# ttn_mad_v2_2.net
KiCad netlist of a schematic drawn in EAGLE
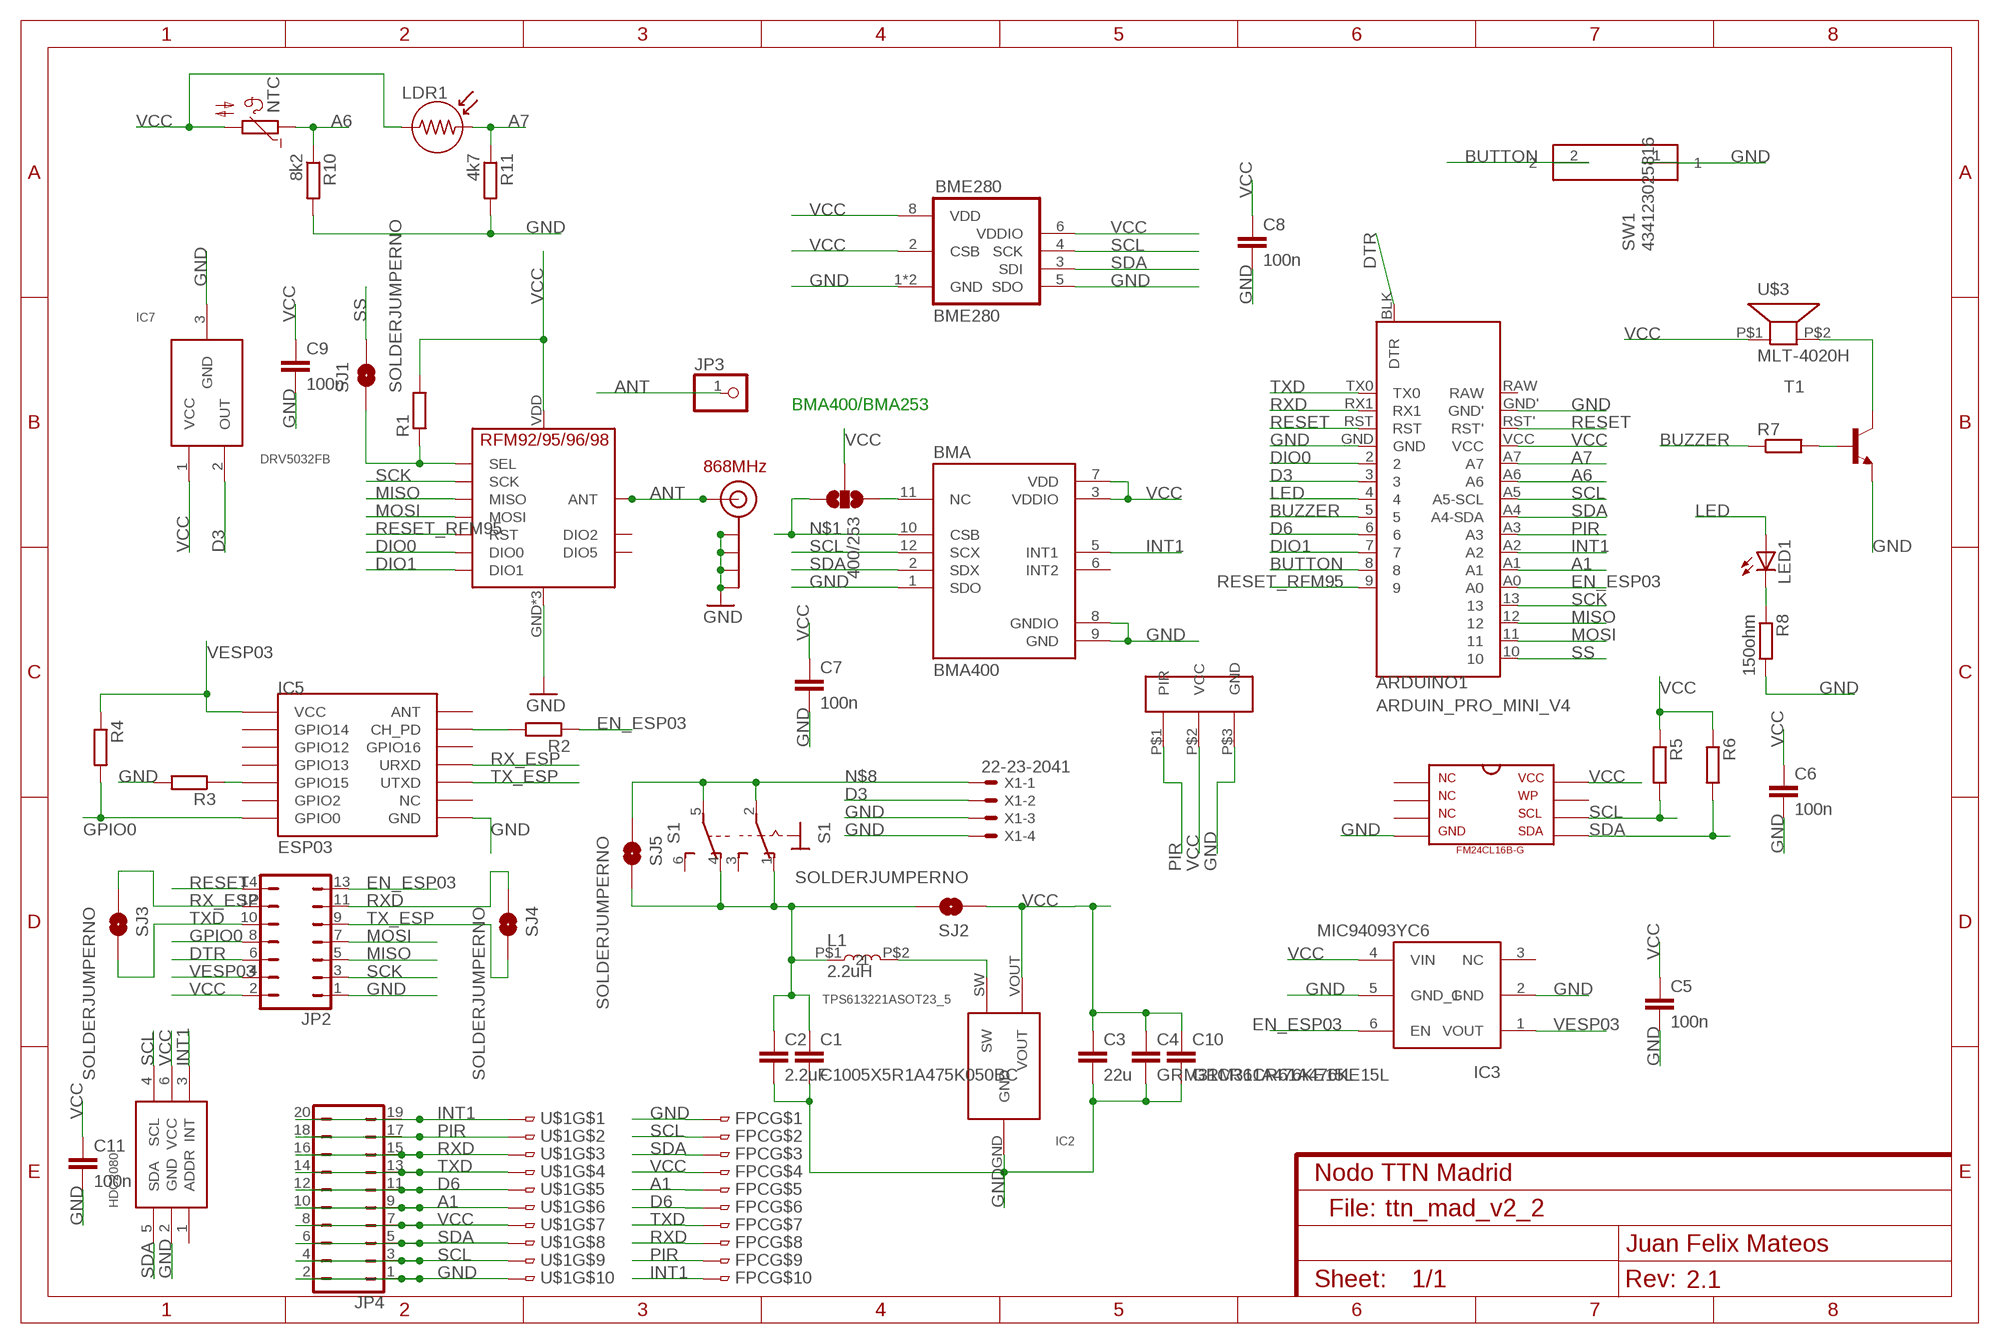
[diagram p0: schematic, sheet 1]

(export (version "E")
  (design (tool "Eeschema 10.0.6"))
  (components
    (comp (ref "400/253")
      (value "SOLDERJUMPER_2WAYT")
      (footprint "eagle-import:SJ_2")
      (libsource (lib "eagle-import") (part "SOLDERJUMPER_2WAYT"))
    )
    (comp (ref "ARDUINO1")
      (value "ARDUIN_PRO_MINI_V4")
      (footprint "eagle-import:ARDUINO_PRO_MINI_V4")
      (libsource (lib "eagle-import") (part "ARDUIN_PRO_MINI_V4"))
    )
    (comp (ref "BMA")
      (value "BMA400")
      (footprint "eagle-import:IC_BMA400")
      (fields (field (name "MF") "Bosch Sensortec"))
      (libsource (lib "eagle-import") (part "BMA400"))
    )
    (comp (ref "BME280")
      (value "BME280")
      (footprint "eagle-import:BME280")
      (libsource (lib "eagle-import") (part "BME280"))
    )
    (comp (ref "C1")
      (value "C1005X5R1A475K050BC")
      (footprint "eagle-import:C0603")
      (libsource (lib "eagle-import") (part "C-EUC0603"))
    )
    (comp (ref "C2")
      (value "2.2uF")
      (footprint "eagle-import:C0603")
      (libsource (lib "eagle-import") (part "C-EUC0603"))
    )
    (comp (ref "C3")
      (value "22u")
      (footprint "eagle-import:C0805")
      (libsource (lib "eagle-import") (part "C-EUC0805"))
    )
    (comp (ref "C4")
      (value "GRM31CR61A476KE15L")
      (footprint "eagle-import:C0805")
      (libsource (lib "eagle-import") (part "C-EUC0805"))
    )
    (comp (ref "C5")
      (value "100n")
      (footprint "eagle-import:C0603")
      (libsource (lib "eagle-import") (part "C-EUC0603"))
    )
    (comp (ref "C6")
      (value "100n")
      (footprint "eagle-import:C0603")
      (libsource (lib "eagle-import") (part "C-EUC0603"))
    )
    (comp (ref "C7")
      (value "100n")
      (footprint "eagle-import:C0603")
      (libsource (lib "eagle-import") (part "C-EUC0603"))
    )
    (comp (ref "C8")
      (value "100n")
      (footprint "eagle-import:C0603")
      (libsource (lib "eagle-import") (part "C-EUC0603"))
    )
    (comp (ref "C9")
      (value "100n")
      (footprint "eagle-import:C0603")
      (libsource (lib "eagle-import") (part "C-EUC0603"))
    )
    (comp (ref "C10")
      (value "GRM31CR61A476KE15L")
      (footprint "eagle-import:C0805")
      (libsource (lib "eagle-import") (part "C-EUC0805"))
    )
    (comp (ref "C11")
      (value "100n")
      (footprint "eagle-import:C0603")
      (libsource (lib "eagle-import") (part "C-EUC0603"))
    )
    (comp (ref "FM24")
      (value "FM24CL16B-G")
      (footprint "eagle-import:FM24CL16B-G")
      (libsource (lib "eagle-import") (part "FM24CL16B-G"))
    )
    (comp (ref "FPC")
      (value "FPC_10P_0_5MM")
      (footprint "eagle-import:FH12-10S-0.5SH")
      (libsource (lib "eagle-import") (part "FPC_10P_0_5MM"))
    )
    (comp (ref "HDC2080")
      (value "HDC2080")
      (footprint "eagle-import:WSON-6")
      (libsource (lib "eagle-import") (part "HDC2080"))
    )
    (comp (ref "IC2")
      (value "TPS613221ASOT23_5")
      (footprint "eagle-import:SOT23-5L")
      (libsource (lib "eagle-import") (part "TPS613221ASOT23_5"))
    )
    (comp (ref "IC3")
      (value "MIC94093YC6")
      (footprint "eagle-import:SC70-6")
      (libsource (lib "eagle-import") (part "MIC94093YC6"))
    )
    (comp (ref "IC5")
      (value "ESP03")
      (footprint "eagle-import:ESP03")
      (libsource (lib "eagle-import") (part "ESP03"))
    )
    (comp (ref "IC7")
      (value "DRV5032FB")
      (footprint "eagle-import:SOT23")
      (libsource (lib "eagle-import") (part "DRV5032FB"))
    )
    (comp (ref "J$2")
      (value "ANTENNATINY")
      (footprint "eagle-import:SMA_UFL_PAD_TINY")
      (libsource (lib "eagle-import") (part "ANTENNATINY"))
    )
    (comp (ref "JP2")
      (value "JP7Q")
      (footprint "eagle-import:JP7Q")
      (libsource (lib "eagle-import") (part "JP7Q"))
    )
    (comp (ref "JP3")
      (value "PINHD-1X1")
      (footprint "eagle-import:1X01")
      (libsource (lib "eagle-import") (part "PINHD-1X1"))
    )
    (comp (ref "JP4")
      (value "JP10Q")
      (footprint "eagle-import:JP10Q")
      (libsource (lib "eagle-import") (part "JP10Q"))
    )
    (comp (ref "L1")
      (value "2.2uH")
      (footprint "eagle-import:SRN2512")
      (libsource (lib "eagle-import") (part "SRN2512"))
    )
    (comp (ref "LDR1")
      (value "LDR")
      (footprint "eagle-import:LDR")
      (libsource (lib "eagle-import") (part "LDR"))
    )
    (comp (ref "LED1")
      (value "LEDSMT1206")
      (footprint "eagle-import:1206")
      (libsource (lib "eagle-import") (part "LEDSMT1206"))
    )
    (comp (ref "NTC")
      (value "NTC640")
      (footprint "eagle-import:P640")
      (libsource (lib "eagle-import") (part "NTC640"))
    )
    (comp (ref "R1")
      (value "R-EU_R0603")
      (footprint "eagle-import:R0603")
      (libsource (lib "eagle-import") (part "R-EU_R0603"))
    )
    (comp (ref "R2")
      (value "R-EU_R0603")
      (footprint "eagle-import:R0603")
      (libsource (lib "eagle-import") (part "R-EU_R0603"))
    )
    (comp (ref "R3")
      (value "R-EU_R0603")
      (footprint "eagle-import:R0603")
      (libsource (lib "eagle-import") (part "R-EU_R0603"))
    )
    (comp (ref "R4")
      (value "R-EU_R0603")
      (footprint "eagle-import:R0603")
      (libsource (lib "eagle-import") (part "R-EU_R0603"))
    )
    (comp (ref "R5")
      (value "R-EU_R0603")
      (footprint "eagle-import:R0603")
      (libsource (lib "eagle-import") (part "R-EU_R0603"))
    )
    (comp (ref "R6")
      (value "R-EU_R0603")
      (footprint "eagle-import:R0603")
      (libsource (lib "eagle-import") (part "R-EU_R0603"))
    )
    (comp (ref "R7")
      (value "R-EU_R0603")
      (footprint "eagle-import:R0603")
      (libsource (lib "eagle-import") (part "R-EU_R0603"))
    )
    (comp (ref "R8")
      (value "150ohm")
      (footprint "eagle-import:R0603")
      (libsource (lib "eagle-import") (part "R-EU_R0603"))
    )
    (comp (ref "R10")
      (value "8k2")
      (footprint "eagle-import:R0603")
      (libsource (lib "eagle-import") (part "R-EU_R0603"))
    )
    (comp (ref "R11")
      (value "4k7")
      (footprint "eagle-import:R0603")
      (libsource (lib "eagle-import") (part "R-EU_R0603"))
    )
    (comp (ref "S1")
      (value "TOGGLE_SWITCHTS_SMD")
      (footprint "eagle-import:TOGGLE_SWITCH_SMD")
      (libsource (lib "eagle-import") (part "TOGGLE_SWITCHTS_SMD"))
    )
    (comp (ref "SJ1")
      (value "SOLDERJUMPERNO")
      (footprint "eagle-import:SJ_2S-NO")
      (libsource (lib "eagle-import") (part "SOLDERJUMPERNO"))
    )
    (comp (ref "SJ2")
      (value "SOLDERJUMPERNO")
      (footprint "eagle-import:SJ_2S-NO")
      (libsource (lib "eagle-import") (part "SOLDERJUMPERNO"))
    )
    (comp (ref "SJ3")
      (value "SOLDERJUMPERNO")
      (footprint "eagle-import:SJ_2S-NO")
      (libsource (lib "eagle-import") (part "SOLDERJUMPERNO"))
    )
    (comp (ref "SJ4")
      (value "SOLDERJUMPERNO")
      (footprint "eagle-import:SJ_2S-NO")
      (libsource (lib "eagle-import") (part "SOLDERJUMPERNO"))
    )
    (comp (ref "SJ5")
      (value "SOLDERJUMPERNO")
      (footprint "eagle-import:SJ_2S-NO")
      (libsource (lib "eagle-import") (part "SOLDERJUMPERNO"))
    )
    (comp (ref "SW1")
      (value "434123025816")
      (footprint "eagle-import:434123025816")
      (libsource (lib "eagle-import") (part "434123025816"))
    )
    (comp (ref "T1")
      (value "BC817-16-NPN-SOT23-BEC")
      (footprint "eagle-import:SOT23-BEC")
      (libsource (lib "eagle-import") (part "-NPN-SOT23-BECBC817-16"))
    )
    (comp (ref "U$1")
      (value "FPC_10P_0_5MM")
      (footprint "eagle-import:FH12-10S-0.5SH")
      (libsource (lib "eagle-import") (part "FPC_10P_0_5MM"))
    )
    (comp (ref "U$3")
      (value "MLT-4020H")
      (footprint "eagle-import:MLT-4020H")
      (libsource (lib "eagle-import") (part "MLT-4020H"))
    )
    (comp (ref "U$5")
      (value "RFM95")
      (footprint "eagle-import:RFM95")
      (libsource (lib "eagle-import") (part "RFM95"))
    )
    (comp (ref "U$6")
      (value "PIR")
      (footprint "eagle-import:PIR")
      (libsource (lib "eagle-import") (part "PIR"))
    )
    (comp (ref "X1")
      (value "22-23-2041")
      (footprint "eagle-import:22-23-2041")
      (fields (field (name "MF") "MOLEX"))
      (libsource (lib "eagle-import") (part "22-23-2041"))
    )
  )
  (nets
    (net (code "1") (name "/A1") (class "Default")
      (node (ref "ARDUINO1") (pin "A1") (pinfunction "A1_A1") (pintype "bidirectional"))
      (node (ref "FPC") (pin "5") (pinfunction "1_5") (pintype "passive"))
      (node (ref "JP4") (pin "10") (pinfunction "10_10") (pintype "passive"))
      (node (ref "JP4") (pin "9") (pinfunction "9_9") (pintype "passive"))
      (node (ref "U$1") (pin "6") (pinfunction "1_6") (pintype "passive"))
    )
    (net (code "2") (name "/A6") (class "Default")
      (node (ref "ARDUINO1") (pin "A6") (pinfunction "A6_A6") (pintype "bidirectional"))
      (node (ref "NTC") (pin "1") (pinfunction "1_1") (pintype "passive"))
      (node (ref "R10") (pin "1") (pinfunction "1_1") (pintype "passive"))
    )
    (net (code "3") (name "/A7") (class "Default")
      (node (ref "ARDUINO1") (pin "A7") (pinfunction "A7_A7") (pintype "bidirectional"))
      (node (ref "LDR1") (pin "2") (pinfunction "2_2") (pintype "passive"))
      (node (ref "R11") (pin "1") (pinfunction "1_1") (pintype "passive"))
    )
    (net (code "4") (name "/ANT") (class "Default")
      (node (ref "J$2") (pin "ANT1") (pinfunction "SIGNAL_ANT1") (pintype "bidirectional"))
      (node (ref "J$2") (pin "ANT2") (pinfunction "SIGNAL_ANT2") (pintype "bidirectional"))
      (node (ref "J$2") (pin "ANT3") (pinfunction "SIGNAL_ANT3") (pintype "bidirectional"))
      (node (ref "JP3") (pin "1") (pinfunction "1_1") (pintype "passive"))
      (node (ref "U$5") (pin "ANT") (pinfunction "ANT_ANT") (pintype "passive"))
    )
    (net (code "5") (name "/BUTTON") (class "Default")
      (node (ref "ARDUINO1") (pin "8") (pinfunction "8_8") (pintype "bidirectional"))
      (node (ref "SW1") (pin "2") (pinfunction "2_2") (pintype "bidirectional"))
    )
    (net (code "6") (name "/BUZZER") (class "Default")
      (node (ref "ARDUINO1") (pin "5") (pinfunction "5_5") (pintype "bidirectional"))
      (node (ref "R7") (pin "1") (pinfunction "1_1") (pintype "passive"))
    )
    (net (code "7") (name "/D3") (class "Default")
      (node (ref "ARDUINO1") (pin "3") (pinfunction "3_3") (pintype "bidirectional"))
      (node (ref "IC7") (pin "2") (pinfunction "OUT_2") (pintype "bidirectional"))
      (node (ref "X1") (pin "2") (pinfunction "S_2") (pintype "passive"))
    )
    (net (code "8") (name "/D6") (class "Default")
      (node (ref "ARDUINO1") (pin "6") (pinfunction "6_6") (pintype "bidirectional"))
      (node (ref "FPC") (pin "6") (pinfunction "1_6") (pintype "passive"))
      (node (ref "JP4") (pin "11") (pinfunction "11_11") (pintype "passive"))
      (node (ref "JP4") (pin "12") (pinfunction "12_12") (pintype "passive"))
      (node (ref "U$1") (pin "5") (pinfunction "1_5") (pintype "passive"))
    )
    (net (code "9") (name "/DIO0") (class "Default")
      (node (ref "ARDUINO1") (pin "2") (pinfunction "2_2") (pintype "bidirectional"))
      (node (ref "U$5") (pin "DIO0") (pinfunction "DIO0_DIO0") (pintype "open_collector"))
    )
    (net (code "10") (name "/DIO1") (class "Default")
      (node (ref "ARDUINO1") (pin "7") (pinfunction "7_7") (pintype "bidirectional"))
      (node (ref "U$5") (pin "DIO1") (pinfunction "DIO1_DIO1") (pintype "open_collector"))
    )
    (net (code "11") (name "/DTR") (class "Default")
      (node (ref "ARDUINO1") (pin "BLK") (pinfunction "DTR_BLK") (pintype "bidirectional"))
      (node (ref "JP2") (pin "6") (pinfunction "6_6") (pintype "passive"))
    )
    (net (code "12") (name "/EN_ESP03") (class "Default")
      (node (ref "ARDUINO1") (pin "A0") (pinfunction "A0_A0") (pintype "bidirectional"))
      (node (ref "IC3") (pin "6") (pinfunction "EN_6") (pintype "bidirectional"))
      (node (ref "JP2") (pin "13") (pinfunction "13_13") (pintype "passive"))
      (node (ref "R2") (pin "1") (pinfunction "1_1") (pintype "passive"))
    )
    (net (code "13") (name "/GPIO0") (class "Default")
      (node (ref "IC5") (pin "GPIO0") (pinfunction "GPIO0_GPIO0") (pintype "bidirectional"))
      (node (ref "JP2") (pin "8") (pinfunction "8_8") (pintype "passive"))
      (node (ref "R4") (pin "2") (pinfunction "2_2") (pintype "passive"))
    )
    (net (code "14") (name "/INT1") (class "Default")
      (node (ref "ARDUINO1") (pin "A2") (pinfunction "A2_A2") (pintype "bidirectional"))
      (node (ref "BMA") (pin "5") (pinfunction "INT1_5") (pintype "bidirectional"))
      (node (ref "FPC") (pin "10") (pinfunction "1_10") (pintype "passive"))
      (node (ref "HDC2080") (pin "3") (pinfunction "INT_3") (pintype "bidirectional"))
      (node (ref "JP4") (pin "19") (pinfunction "19_19") (pintype "passive"))
      (node (ref "JP4") (pin "20") (pinfunction "20_20") (pintype "passive"))
      (node (ref "U$1") (pin "1") (pinfunction "1_1") (pintype "passive"))
    )
    (net (code "15") (name "/LED") (class "Default")
      (node (ref "ARDUINO1") (pin "4") (pinfunction "4_4") (pintype "bidirectional"))
      (node (ref "LED1") (pin "A") (pinfunction "A_A") (pintype "passive"))
    )
    (net (code "16") (name "/MISO") (class "Default")
      (node (ref "ARDUINO1") (pin "12") (pinfunction "12_12") (pintype "bidirectional"))
      (node (ref "JP2") (pin "5") (pinfunction "5_5") (pintype "passive"))
      (node (ref "U$5") (pin "MISO") (pinfunction "MISO_MISO") (pintype "input"))
    )
    (net (code "17") (name "/MOSI") (class "Default")
      (node (ref "ARDUINO1") (pin "11") (pinfunction "11_11") (pintype "bidirectional"))
      (node (ref "JP2") (pin "7") (pinfunction "7_7") (pintype "passive"))
      (node (ref "U$5") (pin "MOSI") (pinfunction "MOSI_MOSI") (pintype "output"))
    )
    (net (code "18") (name "/N$1") (class "Default")
      (node (ref "400/253") (pin "3") (pinfunction "3_3") (pintype "passive"))
      (node (ref "BMA") (pin "10") (pinfunction "CSB_10") (pintype "input"))
    )
    (net (code "19") (name "/N$8") (class "Default")
      (node (ref "S1") (pin "2") (pinfunction "P_2") (pintype "passive"))
      (node (ref "S1") (pin "5") (pinfunction "P_5") (pintype "passive"))
      (node (ref "SJ5") (pin "1") (pinfunction "1_1") (pintype "passive"))
      (node (ref "X1") (pin "1") (pinfunction "S_1") (pintype "passive"))
    )
    (net (code "20") (name "/PIR") (class "Default")
      (node (ref "ARDUINO1") (pin "A3") (pinfunction "A3_A3") (pintype "bidirectional"))
      (node (ref "FPC") (pin "9") (pinfunction "1_9") (pintype "passive"))
      (node (ref "JP4") (pin "17") (pinfunction "17_17") (pintype "passive"))
      (node (ref "JP4") (pin "18") (pinfunction "18_18") (pintype "passive"))
      (node (ref "U$1") (pin "2") (pinfunction "1_2") (pintype "passive"))
      (node (ref "U$6") (pin "P$1") (pinfunction "PIR_P$1") (pintype "bidirectional"))
    )
    (net (code "21") (name "/RESET") (class "Default")
      (node (ref "ARDUINO1") (pin "RST") (pinfunction "RST_RST") (pintype "bidirectional"))
      (node (ref "ARDUINO1") (pin "RST'") (pinfunction "RST'_RST'") (pintype "bidirectional"))
      (node (ref "JP2") (pin "14") (pinfunction "14_14") (pintype "passive"))
    )
    (net (code "22") (name "/RESET_RFM95") (class "Default")
      (node (ref "ARDUINO1") (pin "9") (pinfunction "9_9") (pintype "bidirectional"))
      (node (ref "U$5") (pin "RST") (pinfunction "RST_RST") (pintype "open_collector"))
    )
    (net (code "23") (name "/RXD") (class "Default")
      (node (ref "ARDUINO1") (pin "RX1") (pinfunction "RX1_RX1") (pintype "bidirectional"))
      (node (ref "FPC") (pin "8") (pinfunction "1_8") (pintype "passive"))
      (node (ref "JP2") (pin "11") (pinfunction "11_11") (pintype "passive"))
      (node (ref "JP4") (pin "15") (pinfunction "15_15") (pintype "passive"))
      (node (ref "JP4") (pin "16") (pinfunction "16_16") (pintype "passive"))
      (node (ref "SJ4") (pin "1") (pinfunction "1_1") (pintype "passive"))
      (node (ref "U$1") (pin "3") (pinfunction "1_3") (pintype "passive"))
    )
    (net (code "24") (name "/RX_ESP") (class "Default")
      (node (ref "IC5") (pin "URXD") (pinfunction "URXD_URXD") (pintype "bidirectional"))
      (node (ref "JP2") (pin "12") (pinfunction "12_12") (pintype "passive"))
      (node (ref "SJ3") (pin "1") (pinfunction "1_1") (pintype "passive"))
    )
    (net (code "25") (name "/SCK") (class "Default")
      (node (ref "ARDUINO1") (pin "13") (pinfunction "13_13") (pintype "bidirectional"))
      (node (ref "JP2") (pin "3") (pinfunction "3_3") (pintype "passive"))
      (node (ref "U$5") (pin "SCK") (pinfunction "SCK_SCK") (pintype "input"))
    )
    (net (code "26") (name "/SCL") (class "Default")
      (node (ref "ARDUINO1") (pin "A5") (pinfunction "A5-SCL_A5") (pintype "bidirectional"))
      (node (ref "BMA") (pin "12") (pinfunction "SCX_12") (pintype "input"))
      (node (ref "BME280") (pin "4") (pinfunction "SCK_4") (pintype "bidirectional"))
      (node (ref "FM24") (pin "6") (pinfunction "6_6") (pintype "input"))
      (node (ref "FPC") (pin "2") (pinfunction "1_2") (pintype "passive"))
      (node (ref "HDC2080") (pin "4") (pinfunction "SCL_4") (pintype "bidirectional"))
      (node (ref "JP4") (pin "3") (pinfunction "3_3") (pintype "passive"))
      (node (ref "JP4") (pin "4") (pinfunction "4_4") (pintype "passive"))
      (node (ref "R5") (pin "2") (pinfunction "2_2") (pintype "passive"))
      (node (ref "U$1") (pin "9") (pinfunction "1_9") (pintype "passive"))
    )
    (net (code "27") (name "/SDA") (class "Default")
      (node (ref "ARDUINO1") (pin "A4") (pinfunction "A4-SDA_A4") (pintype "bidirectional"))
      (node (ref "BMA") (pin "2") (pinfunction "SDX_2") (pintype "bidirectional"))
      (node (ref "BME280") (pin "3") (pinfunction "SDI_3") (pintype "bidirectional"))
      (node (ref "FM24") (pin "5") (pinfunction "5_5") (pintype "input"))
      (node (ref "FPC") (pin "3") (pinfunction "1_3") (pintype "passive"))
      (node (ref "HDC2080") (pin "5") (pinfunction "SDA_5") (pintype "bidirectional"))
      (node (ref "JP4") (pin "5") (pinfunction "5_5") (pintype "passive"))
      (node (ref "JP4") (pin "6") (pinfunction "6_6") (pintype "passive"))
      (node (ref "R6") (pin "2") (pinfunction "2_2") (pintype "passive"))
      (node (ref "U$1") (pin "8") (pinfunction "1_8") (pintype "passive"))
    )
    (net (code "28") (name "/SS") (class "Default")
      (node (ref "ARDUINO1") (pin "10") (pinfunction "10_10") (pintype "bidirectional"))
      (node (ref "SJ1") (pin "2") (pinfunction "2_2") (pintype "passive"))
    )
    (net (code "29") (name "/TXD") (class "Default")
      (node (ref "ARDUINO1") (pin "TX0") (pinfunction "TX0_TX0") (pintype "bidirectional"))
      (node (ref "FPC") (pin "7") (pinfunction "1_7") (pintype "passive"))
      (node (ref "JP2") (pin "10") (pinfunction "10_10") (pintype "passive"))
      (node (ref "JP4") (pin "13") (pinfunction "13_13") (pintype "passive"))
      (node (ref "JP4") (pin "14") (pinfunction "14_14") (pintype "passive"))
      (node (ref "SJ3") (pin "2") (pinfunction "2_2") (pintype "passive"))
      (node (ref "U$1") (pin "4") (pinfunction "1_4") (pintype "passive"))
    )
    (net (code "30") (name "/TX_ESP") (class "Default")
      (node (ref "IC5") (pin "UTXD") (pinfunction "UTXD_UTXD") (pintype "bidirectional"))
      (node (ref "JP2") (pin "9") (pinfunction "9_9") (pintype "passive"))
      (node (ref "SJ4") (pin "2") (pinfunction "2_2") (pintype "passive"))
    )
    (net (code "31") (name "/VCC") (class "Default")
      (node (ref "400/253") (pin "2") (pinfunction "2_2") (pintype "passive"))
      (node (ref "ARDUINO1") (pin "VCC") (pinfunction "VCC_VCC") (pintype "bidirectional"))
      (node (ref "BMA") (pin "3") (pinfunction "VDDIO_3") (pintype "power_in"))
      (node (ref "BMA") (pin "7") (pinfunction "VDD_7") (pintype "power_in"))
      (node (ref "BME280") (pin "2") (pinfunction "CSB_2") (pintype "input"))
      (node (ref "BME280") (pin "6") (pinfunction "VDDIO_6") (pintype "power_in"))
      (node (ref "BME280") (pin "8") (pinfunction "VDD_8") (pintype "power_in"))
      (node (ref "C10") (pin "1") (pinfunction "1_1") (pintype "passive"))
      (node (ref "C11") (pin "1") (pinfunction "1_1") (pintype "passive"))
      (node (ref "C3") (pin "1") (pinfunction "1_1") (pintype "passive"))
      (node (ref "C4") (pin "1") (pinfunction "1_1") (pintype "passive"))
      (node (ref "C5") (pin "1") (pinfunction "1_1") (pintype "passive"))
      (node (ref "C6") (pin "1") (pinfunction "1_1") (pintype "passive"))
      (node (ref "C7") (pin "1") (pinfunction "1_1") (pintype "passive"))
      (node (ref "C8") (pin "1") (pinfunction "1_1") (pintype "passive"))
      (node (ref "C9") (pin "1") (pinfunction "1_1") (pintype "passive"))
      (node (ref "FM24") (pin "8") (pinfunction "8_8") (pintype "power_in"))
      (node (ref "FPC") (pin "4") (pinfunction "1_4") (pintype "passive"))
      (node (ref "HDC2080") (pin "6") (pinfunction "VCC_6") (pintype "bidirectional"))
      (node (ref "IC2") (pin "VOUT") (pinfunction "VOUT_VOUT") (pintype "bidirectional"))
      (node (ref "IC3") (pin "4") (pinfunction "VIN_4") (pintype "bidirectional"))
      (node (ref "IC7") (pin "1") (pinfunction "VCC_1") (pintype "bidirectional"))
      (node (ref "JP2") (pin "2") (pinfunction "2_2") (pintype "passive"))
      (node (ref "JP4") (pin "7") (pinfunction "7_7") (pintype "passive"))
      (node (ref "JP4") (pin "8") (pinfunction "8_8") (pintype "passive"))
      (node (ref "LDR1") (pin "1") (pinfunction "1_1") (pintype "passive"))
      (node (ref "NTC") (pin "2") (pinfunction "2_2") (pintype "passive"))
      (node (ref "R1") (pin "2") (pinfunction "2_2") (pintype "passive"))
      (node (ref "R5") (pin "1") (pinfunction "1_1") (pintype "passive"))
      (node (ref "R6") (pin "1") (pinfunction "1_1") (pintype "passive"))
      (node (ref "SJ2") (pin "1") (pinfunction "1_1") (pintype "passive"))
      (node (ref "U$1") (pin "7") (pinfunction "1_7") (pintype "passive"))
      (node (ref "U$3") (pin "P$1") (pinfunction "1_P$1") (pintype "passive"))
      (node (ref "U$5") (pin "VDD") (pinfunction "VCC_VDD") (pintype "power_in"))
      (node (ref "U$6") (pin "P$2") (pinfunction "VCC_P$2") (pintype "bidirectional"))
    )
    (net (code "32") (name "/VESP03") (class "Default")
      (node (ref "IC3") (pin "1") (pinfunction "VOUT_1") (pintype "bidirectional"))
      (node (ref "IC5") (pin "VCC") (pinfunction "VCC_VCC") (pintype "bidirectional"))
      (node (ref "JP2") (pin "4") (pinfunction "4_4") (pintype "passive"))
      (node (ref "R4") (pin "1") (pinfunction "1_1") (pintype "passive"))
    )
    (net (code "33") (name "GND") (class "Default")
      (node (ref "ARDUINO1") (pin "GND") (pinfunction "GND_GND") (pintype "bidirectional"))
      (node (ref "ARDUINO1") (pin "GND'") (pinfunction "GND'_GND'") (pintype "bidirectional"))
      (node (ref "BMA") (pin "1") (pinfunction "SDO_1") (pintype "bidirectional"))
      (node (ref "BMA") (pin "8") (pinfunction "GNDIO_8") (pintype "power_in"))
      (node (ref "BMA") (pin "9") (pinfunction "GND_9") (pintype "power_in"))
      (node (ref "BME280") (pin "1") (pinfunction "GND_1") (pintype "power_in"))
      (node (ref "BME280") (pin "5") (pinfunction "SDO_5") (pintype "input"))
      (node (ref "BME280") (pin "7") (pinfunction "GND_7") (pintype "power_in"))
      (node (ref "C1") (pin "2") (pinfunction "2_2") (pintype "passive"))
      (node (ref "C10") (pin "2") (pinfunction "2_2") (pintype "passive"))
      (node (ref "C11") (pin "2") (pinfunction "2_2") (pintype "passive"))
      (node (ref "C2") (pin "2") (pinfunction "2_2") (pintype "passive"))
      (node (ref "C3") (pin "2") (pinfunction "2_2") (pintype "passive"))
      (node (ref "C4") (pin "2") (pinfunction "2_2") (pintype "passive"))
      (node (ref "C5") (pin "2") (pinfunction "2_2") (pintype "passive"))
      (node (ref "C6") (pin "2") (pinfunction "2_2") (pintype "passive"))
      (node (ref "C7") (pin "2") (pinfunction "2_2") (pintype "passive"))
      (node (ref "C8") (pin "2") (pinfunction "2_2") (pintype "passive"))
      (node (ref "C9") (pin "2") (pinfunction "2_2") (pintype "passive"))
      (node (ref "FM24") (pin "4") (pinfunction "4_4") (pintype "power_in"))
      (node (ref "FPC") (pin "1") (pinfunction "1_1") (pintype "passive"))
      (node (ref "HDC2080") (pin "2") (pinfunction "GND_2") (pintype "bidirectional"))
      (node (ref "IC2") (pin "GND") (pinfunction "GND_GND") (pintype "bidirectional"))
      (node (ref "IC3") (pin "2") (pinfunction "GND_2") (pintype "bidirectional"))
      (node (ref "IC3") (pin "5") (pinfunction "GND_1_5") (pintype "bidirectional"))
      (node (ref "IC5") (pin "GND") (pinfunction "GND_GND") (pintype "bidirectional"))
      (node (ref "IC7") (pin "3") (pinfunction "GND_3") (pintype "bidirectional"))
      (node (ref "J$2") (pin "GND1") (pinfunction "GND_GND1") (pintype "bidirectional"))
      (node (ref "J$2") (pin "GND2") (pinfunction "GND_GND2") (pintype "bidirectional"))
      (node (ref "J$2") (pin "GND3") (pinfunction "GND_GND3") (pintype "bidirectional"))
      (node (ref "J$2") (pin "GND4") (pinfunction "GND_GND4") (pintype "bidirectional"))
      (node (ref "JP2") (pin "1") (pinfunction "1_1") (pintype "passive"))
      (node (ref "JP4") (pin "1") (pinfunction "1_1") (pintype "passive"))
      (node (ref "JP4") (pin "2") (pinfunction "2_2") (pintype "passive"))
      (node (ref "R10") (pin "2") (pinfunction "2_2") (pintype "passive"))
      (node (ref "R11") (pin "2") (pinfunction "2_2") (pintype "passive"))
      (node (ref "R3") (pin "2") (pinfunction "2_2") (pintype "passive"))
      (node (ref "R8") (pin "2") (pinfunction "2_2") (pintype "passive"))
      (node (ref "SW1") (pin "1") (pinfunction "1_1") (pintype "bidirectional"))
      (node (ref "T1") (pin "E") (pinfunction "E_E") (pintype "passive"))
      (node (ref "U$1") (pin "10") (pinfunction "1_10") (pintype "passive"))
      (node (ref "U$5") (pin "GND") (pinfunction "GND_GND") (pintype "power_in"))
      (node (ref "U$5") (pin "GND1") (pinfunction "GND_GND1") (pintype "power_in"))
      (node (ref "U$5") (pin "GND2") (pinfunction "GND_GND2") (pintype "power_in"))
      (node (ref "U$6") (pin "P$3") (pinfunction "GND_P$3") (pintype "bidirectional"))
      (node (ref "X1") (pin "3") (pinfunction "S_3") (pintype "passive"))
      (node (ref "X1") (pin "4") (pinfunction "S_4") (pintype "passive"))
    )
    (net (code "34") (name "Net-(BMA-NC)") (class "Default")
      (node (ref "400/253") (pin "1") (pinfunction "1_1") (pintype "passive"))
      (node (ref "BMA") (pin "11") (pinfunction "NC_11") (pintype "input"))
    )
    (net (code "35") (name "Net-(IC5-PadCH_PD)") (class "Default")
      (node (ref "IC5") (pin "CH_PD") (pinfunction "CH_PD_CH_PD") (pintype "bidirectional"))
      (node (ref "R2") (pin "2") (pinfunction "2_2") (pintype "passive"))
    )
    (net (code "36") (name "Net-(IC5-PadGPIO15)") (class "Default")
      (node (ref "IC5") (pin "GPIO15") (pinfunction "GPIO15_GPIO15") (pintype "bidirectional"))
      (node (ref "R3") (pin "1") (pinfunction "1_1") (pintype "passive"))
    )
    (net (code "37") (name "Net-(L1-1)") (class "Default")
      (node (ref "C1") (pin "1") (pinfunction "1_1") (pintype "passive"))
      (node (ref "C2") (pin "1") (pinfunction "1_1") (pintype "passive"))
      (node (ref "L1") (pin "P$1") (pinfunction "1_P$1") (pintype "passive"))
      (node (ref "S1") (pin "1") (pinfunction "O_1") (pintype "passive"))
      (node (ref "S1") (pin "4") (pinfunction "O_4") (pintype "passive"))
      (node (ref "SJ2") (pin "2") (pinfunction "2_2") (pintype "passive"))
      (node (ref "SJ5") (pin "2") (pinfunction "2_2") (pintype "passive"))
    )
    (net (code "38") (name "Net-(L1-2)") (class "Default")
      (node (ref "IC2") (pin "SW") (pinfunction "SW_SW") (pintype "bidirectional"))
      (node (ref "L1") (pin "P$2") (pinfunction "2_P$2") (pintype "passive"))
    )
    (net (code "39") (name "Net-(LED1-PadC)") (class "Default")
      (node (ref "LED1") (pin "C") (pinfunction "C_C") (pintype "passive"))
      (node (ref "R8") (pin "1") (pinfunction "1_1") (pintype "passive"))
    )
    (net (code "40") (name "Net-(R7-Pad2)") (class "Default")
      (node (ref "R7") (pin "2") (pinfunction "2_2") (pintype "passive"))
      (node (ref "T1") (pin "B") (pinfunction "B_B") (pintype "passive"))
    )
    (net (code "41") (name "Net-(U$3-2)") (class "Default")
      (node (ref "T1") (pin "C") (pinfunction "C_C") (pintype "passive"))
      (node (ref "U$3") (pin "P$2") (pinfunction "2_P$2") (pintype "passive"))
    )
    (net (code "42") (name "Net-(U$5-SEL)") (class "Default")
      (node (ref "R1") (pin "1") (pinfunction "1_1") (pintype "passive"))
      (node (ref "SJ1") (pin "1") (pinfunction "1_1") (pintype "passive"))
      (node (ref "U$5") (pin "NSS") (pinfunction "SEL_NSS") (pintype "input"))
    )
    (net (code "43") (name "unconnected-(ARDUINO1-PadRAW)") (class "Default")
      (node (ref "ARDUINO1") (pin "RAW") (pinfunction "RAW_RAW") (pintype "bidirectional"))
    )
    (net (code "44") (name "unconnected-(BMA-INT2-Pad6)") (class "Default")
      (node (ref "BMA") (pin "6") (pinfunction "INT2_6") (pintype "bidirectional"))
    )
    (net (code "45") (name "unconnected-(FM24-Pad1)") (class "Default")
      (node (ref "FM24") (pin "1") (pinfunction "1_1") (pintype "no_connect"))
    )
    (net (code "46") (name "unconnected-(FM24-Pad2)") (class "Default")
      (node (ref "FM24") (pin "2") (pinfunction "2_2") (pintype "no_connect"))
    )
    (net (code "47") (name "unconnected-(FM24-Pad3)") (class "Default")
      (node (ref "FM24") (pin "3") (pinfunction "3_3") (pintype "no_connect"))
    )
    (net (code "48") (name "unconnected-(FM24-Pad7)") (class "Default")
      (node (ref "FM24") (pin "7") (pinfunction "7_7") (pintype "bidirectional"))
    )
    (net (code "49") (name "unconnected-(HDC2080-ADDR-Pad1)") (class "Default")
      (node (ref "HDC2080") (pin "1") (pinfunction "ADDR_1") (pintype "bidirectional"))
    )
    (net (code "50") (name "unconnected-(IC3-NC-Pad3)") (class "Default")
      (node (ref "IC3") (pin "3") (pinfunction "NC_3") (pintype "bidirectional"))
    )
    (net (code "51") (name "unconnected-(IC5-GPIO16-PadGPIO18)") (class "Default")
      (node (ref "IC5") (pin "GPIO18") (pinfunction "GPIO16_GPIO18") (pintype "bidirectional"))
    )
    (net (code "52") (name "unconnected-(IC5-PadANT)") (class "Default")
      (node (ref "IC5") (pin "ANT") (pinfunction "ANT_ANT") (pintype "bidirectional"))
    )
    (net (code "53") (name "unconnected-(IC5-PadGPIO2)") (class "Default")
      (node (ref "IC5") (pin "GPIO2") (pinfunction "GPIO2_GPIO2") (pintype "bidirectional"))
    )
    (net (code "54") (name "unconnected-(IC5-PadGPIO12)") (class "Default")
      (node (ref "IC5") (pin "GPIO12") (pinfunction "GPIO12_GPIO12") (pintype "bidirectional"))
    )
    (net (code "55") (name "unconnected-(IC5-PadGPIO13)") (class "Default")
      (node (ref "IC5") (pin "GPIO13") (pinfunction "GPIO13_GPIO13") (pintype "bidirectional"))
    )
    (net (code "56") (name "unconnected-(IC5-PadGPIO14)") (class "Default")
      (node (ref "IC5") (pin "GPIO14") (pinfunction "GPIO14_GPIO14") (pintype "bidirectional"))
    )
    (net (code "57") (name "unconnected-(IC5-PadNC)") (class "Default")
      (node (ref "IC5") (pin "NC") (pinfunction "NC_NC") (pintype "bidirectional"))
    )
    (net (code "58") (name "unconnected-(S1A-S-Pad3)") (class "Default")
      (node (ref "S1") (pin "3") (pinfunction "S_3") (pintype "passive"))
    )
    (net (code "59") (name "unconnected-(S1B-S-Pad6)") (class "Default")
      (node (ref "S1") (pin "6") (pinfunction "S_6") (pintype "passive"))
    )
    (net (code "60") (name "unconnected-(U$5-PadDIO2)") (class "Default")
      (node (ref "U$5") (pin "DIO2") (pinfunction "DIO2_DIO2") (pintype "open_collector"))
    )
    (net (code "61") (name "unconnected-(U$5-PadDIO5)") (class "Default")
      (node (ref "U$5") (pin "DIO5") (pinfunction "DIO5_DIO5") (pintype "open_collector"))
    )
  )
)
